# Sche.net
KiCad netlist of a schematic drawn in Altium Designer
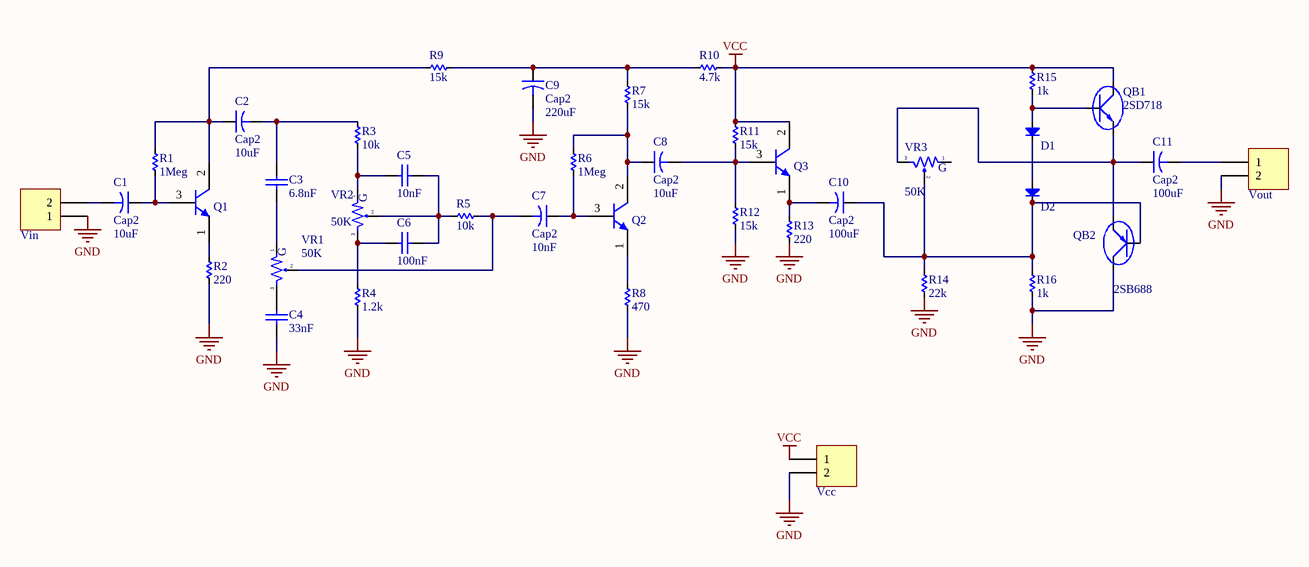
[diagram p0: Sche.SchDoc]

(export (version "E")
  (design (tool "Eeschema 10.0.6"))
  (components
    (comp (ref "C1")
      (value "Cap2")
      (footprint "CAPR5-4X5")
      (description "Capacitor")
      (fields (field (name "ALTIUM_VALUE") "10uF") (field (name "PUBLISHER") "Altium Limited"))
      (libsource (lib "Miscellaneous Devices") (part "Cap2"))
    )
    (comp (ref "C2")
      (value "Cap2")
      (footprint "CAPR5-4X5")
      (description "Capacitor")
      (fields (field (name "ALTIUM_VALUE") "10uF") (field (name "PUBLISHER") "Altium Limited"))
      (libsource (lib "Miscellaneous Devices") (part "Cap2"))
    )
    (comp (ref "C3")
      (value "6.8nF")
      (footprint "CN1.5")
      (description "Capacitor")
      (fields (field (name "Comment") "Cap Non-Pol"))
      (libsource (lib "PIF_Library") (part "Cap Non-Pol"))
    )
    (comp (ref "C4")
      (value "33nF")
      (footprint "CN1.5")
      (description "Capacitor")
      (fields (field (name "Comment") "Cap Non-Pol"))
      (libsource (lib "PIF_Library") (part "Cap Non-Pol"))
    )
    (comp (ref "C5")
      (value "10nF")
      (footprint "CN1.5")
      (description "Capacitor")
      (fields (field (name "Comment") "Cap Non-Pol"))
      (libsource (lib "PIF_Library") (part "Cap Non-Pol"))
    )
    (comp (ref "C6")
      (value "100nF")
      (footprint "CN1.5")
      (description "Capacitor")
      (fields (field (name "Comment") "Cap Non-Pol"))
      (libsource (lib "PIF_Library") (part "Cap Non-Pol"))
    )
    (comp (ref "C7")
      (value "Cap2")
      (footprint "CAPR5-4X5")
      (description "Capacitor")
      (fields (field (name "ALTIUM_VALUE") "10nF") (field (name "PUBLISHER") "Altium Limited"))
      (libsource (lib "Miscellaneous Devices") (part "Cap2"))
    )
    (comp (ref "C8")
      (value "Cap2")
      (footprint "CAPR5-4X5")
      (description "Capacitor")
      (fields (field (name "ALTIUM_VALUE") "10uF") (field (name "PUBLISHER") "Altium Limited"))
      (libsource (lib "Miscellaneous Devices") (part "Cap2"))
    )
    (comp (ref "C9")
      (value "Cap2")
      (footprint "CAPR5-4X5")
      (description "Capacitor")
      (fields (field (name "ALTIUM_VALUE") "220uF") (field (name "PUBLISHER") "Altium Limited"))
      (libsource (lib "Miscellaneous Devices") (part "Cap2"))
    )
    (comp (ref "C10")
      (value "Cap2")
      (footprint "CAPR5-4X5")
      (description "Capacitor")
      (fields (field (name "ALTIUM_VALUE") "100uF") (field (name "PUBLISHER") "Altium Limited"))
      (libsource (lib "Miscellaneous Devices") (part "Cap2"))
    )
    (comp (ref "C11")
      (value "Cap2")
      (footprint "CAPR5-4X5")
      (description "Capacitor")
      (fields (field (name "ALTIUM_VALUE") "100uF") (field (name "PUBLISHER") "Altium Limited"))
      (libsource (lib "Miscellaneous Devices") (part "Cap2"))
    )
    (comp (ref "D1")
      (value "Diode")
      (footprint "DIO-1A")
      (description "Default Diode")
      (fields (field (name "PUBLISHER") "Altium Limited"))
      (libsource (lib "LIBRARY") (part "Diode"))
    )
    (comp (ref "D2")
      (value "Diode")
      (footprint "DIO-1A")
      (description "Default Diode")
      (fields (field (name "PUBLISHER") "Altium Limited"))
      (libsource (lib "LIBRARY") (part "Diode"))
    )
    (comp (ref "Q1")
      (value "C1815")
      (footprint "QTO-92")
      (description "NPN Bipolar Transistor")
      (libsource (lib "PIF_Library") (part "C1815"))
    )
    (comp (ref "Q2")
      (value "C1815")
      (footprint "QTO-92")
      (description "NPN Bipolar Transistor")
      (libsource (lib "PIF_Library") (part "C1815"))
    )
    (comp (ref "Q3")
      (value "C1815")
      (footprint "QTO-92")
      (description "NPN Bipolar Transistor")
      (libsource (lib "PIF_Library") (part "C1815"))
    )
    (comp (ref "QB1")
      (value "2SD718")
      (footprint "TO247h")
      (description "Transistor Power Supply")
      (libsource (lib "LIBRARY") (part "2SC5200"))
    )
    (comp (ref "QB2")
      (value "2SB688")
      (footprint "TO247h")
      (description "Transistor Power Supply")
      (libsource (lib "LIBRARY") (part "2SB688"))
    )
    (comp (ref "R1")
      (value "1Meg")
      (footprint "RES-SMD-0805")
      (description "Resistor")
      (fields
        (field (name "MANUFACTURER") "Generic Components")
        (field (name "PUBLISHER") "Altium Hobart Technology Centre")
      )
      (libsource (lib "LIBRARY") (part "Res-SMD"))
    )
    (comp (ref "R2")
      (value "220")
      (footprint "RES-SMD-0805")
      (description "Resistor")
      (fields
        (field (name "MANUFACTURER") "Generic Components")
        (field (name "PUBLISHER") "Altium Hobart Technology Centre")
      )
      (libsource (lib "LIBRARY") (part "Res-SMD"))
    )
    (comp (ref "R3")
      (value "10k")
      (footprint "RES-SMD-0805")
      (description "Resistor")
      (fields
        (field (name "MANUFACTURER") "Generic Components")
        (field (name "PUBLISHER") "Altium Hobart Technology Centre")
      )
      (libsource (lib "LIBRARY") (part "Res-SMD"))
    )
    (comp (ref "R4")
      (value "1.2k")
      (footprint "RES-SMD-0805")
      (description "Resistor")
      (fields
        (field (name "MANUFACTURER") "Generic Components")
        (field (name "PUBLISHER") "Altium Hobart Technology Centre")
      )
      (libsource (lib "LIBRARY") (part "Res-SMD"))
    )
    (comp (ref "R5")
      (value "10k")
      (footprint "RES-SMD-0805")
      (description "Resistor")
      (fields
        (field (name "MANUFACTURER") "Generic Components")
        (field (name "PUBLISHER") "Altium Hobart Technology Centre")
      )
      (libsource (lib "LIBRARY") (part "Res-SMD"))
    )
    (comp (ref "R6")
      (value "1Meg")
      (footprint "RES-SMD-0805")
      (description "Resistor")
      (fields
        (field (name "MANUFACTURER") "Generic Components")
        (field (name "PUBLISHER") "Altium Hobart Technology Centre")
      )
      (libsource (lib "LIBRARY") (part "Res-SMD"))
    )
    (comp (ref "R7")
      (value "15k")
      (footprint "RES-SMD-0805")
      (description "Resistor")
      (fields
        (field (name "MANUFACTURER") "Generic Components")
        (field (name "PUBLISHER") "Altium Hobart Technology Centre")
      )
      (libsource (lib "LIBRARY") (part "Res-SMD"))
    )
    (comp (ref "R8")
      (value "470")
      (footprint "RES-SMD-0805")
      (description "Resistor")
      (fields
        (field (name "MANUFACTURER") "Generic Components")
        (field (name "PUBLISHER") "Altium Hobart Technology Centre")
      )
      (libsource (lib "LIBRARY") (part "Res-SMD"))
    )
    (comp (ref "R9")
      (value "15k")
      (footprint "RES-SMD-0805")
      (description "Resistor")
      (fields
        (field (name "MANUFACTURER") "Generic Components")
        (field (name "PUBLISHER") "Altium Hobart Technology Centre")
      )
      (libsource (lib "LIBRARY") (part "Res-SMD"))
    )
    (comp (ref "R10")
      (value "4.7k")
      (footprint "RES-SMD-0805")
      (description "Resistor")
      (fields
        (field (name "MANUFACTURER") "Generic Components")
        (field (name "PUBLISHER") "Altium Hobart Technology Centre")
      )
      (libsource (lib "LIBRARY") (part "Res-SMD"))
    )
    (comp (ref "R11")
      (value "15k")
      (footprint "RES-SMD-0805")
      (description "Resistor")
      (fields
        (field (name "MANUFACTURER") "Generic Components")
        (field (name "PUBLISHER") "Altium Hobart Technology Centre")
      )
      (libsource (lib "LIBRARY") (part "Res-SMD"))
    )
    (comp (ref "R12")
      (value "15k")
      (footprint "RES-SMD-0805")
      (description "Resistor")
      (fields
        (field (name "MANUFACTURER") "Generic Components")
        (field (name "PUBLISHER") "Altium Hobart Technology Centre")
      )
      (libsource (lib "LIBRARY") (part "Res-SMD"))
    )
    (comp (ref "R13")
      (value "220")
      (footprint "RES-SMD-0805")
      (description "Resistor")
      (fields
        (field (name "MANUFACTURER") "Generic Components")
        (field (name "PUBLISHER") "Altium Hobart Technology Centre")
      )
      (libsource (lib "LIBRARY") (part "Res-SMD"))
    )
    (comp (ref "R14")
      (value "22k")
      (footprint "RES-SMD-0805")
      (description "Resistor")
      (fields
        (field (name "MANUFACTURER") "Generic Components")
        (field (name "PUBLISHER") "Altium Hobart Technology Centre")
      )
      (libsource (lib "LIBRARY") (part "Res-SMD"))
    )
    (comp (ref "R15")
      (value "1k")
      (footprint "RES-SMD-0805")
      (description "Resistor")
      (fields
        (field (name "MANUFACTURER") "Generic Components")
        (field (name "PUBLISHER") "Altium Hobart Technology Centre")
      )
      (libsource (lib "LIBRARY") (part "Res-SMD"))
    )
    (comp (ref "R16")
      (value "1k")
      (footprint "RES-SMD-0805")
      (description "Resistor")
      (fields
        (field (name "MANUFACTURER") "Generic Components")
        (field (name "PUBLISHER") "Altium Hobart Technology Centre")
      )
      (libsource (lib "LIBRARY") (part "Res-SMD"))
    )
    (comp (ref "Vcc")
      (value "Domino 2")
      (footprint "DOMINO 2- 5mm")
      (description "Domino, 2-Pin")
      (fields (field (name "PUBLISHER") "Altium Limited"))
      (libsource (lib "PIF_Library") (part "Domino 2"))
    )
    (comp (ref "Vin")
      (value "Domino 2")
      (footprint "DOMINO 2- 5mm")
      (description "Domino, 2-Pin")
      (fields (field (name "PUBLISHER") "Altium Limited"))
      (libsource (lib "") (part "Domino 2_1"))
    )
    (comp (ref "Vout")
      (value "Domino 2")
      (footprint "DOMINO 2- 5mm")
      (description "Domino, 2-Pin")
      (fields (field (name "PUBLISHER") "Altium Limited"))
      (libsource (lib "PIF_Library") (part "Domino 2"))
    )
    (comp (ref "VR1")
      (value "50K")
      (footprint "VR-S1")
      (description "Var Resistor")
      (libsource (lib "LIBRARY") (part "VR-S"))
    )
    (comp (ref "VR2")
      (value "50K")
      (footprint "VR-S1")
      (description "Var Resistor")
      (libsource (lib "LIBRARY") (part "VR-S"))
    )
    (comp (ref "VR3")
      (value "50K")
      (footprint "VR-S1")
      (description "Var Resistor")
      (libsource (lib "LIBRARY") (part "VR-S"))
    )
  )
  (nets
    (net (code "1") (name "GND") (class "Default")
      (node (ref "C4") (pin "1") (pinfunction "1_1") (pintype "passive"))
      (node (ref "C9") (pin "2") (pinfunction "2_2") (pintype "passive"))
      (node (ref "QB2") (pin "2") (pinfunction "C_2") (pintype "passive"))
      (node (ref "R12") (pin "2") (pinfunction "2_2") (pintype "passive"))
      (node (ref "R13") (pin "2") (pinfunction "2_2") (pintype "passive"))
      (node (ref "R14") (pin "2") (pinfunction "2_2") (pintype "passive"))
      (node (ref "R16") (pin "2") (pinfunction "2_2") (pintype "passive"))
      (node (ref "R2") (pin "2") (pinfunction "2_2") (pintype "passive"))
      (node (ref "R4") (pin "2") (pinfunction "2_2") (pintype "passive"))
      (node (ref "R8") (pin "2") (pinfunction "2_2") (pintype "passive"))
      (node (ref "Vcc") (pin "2") (pinfunction "2_2") (pintype "passive"))
      (node (ref "Vin") (pin "1") (pinfunction "1_1") (pintype "passive"))
      (node (ref "Vout") (pin "2") (pinfunction "2_2") (pintype "passive"))
    )
    (net (code "2") (name "Net-(C1-Pad2)") (class "Default")
      (node (ref "C1") (pin "2") (pinfunction "2_2") (pintype "passive"))
      (node (ref "Vin") (pin "2") (pinfunction "2_2") (pintype "passive"))
    )
    (net (code "3") (name "Net-(C2-Pad2)") (class "Default")
      (node (ref "C2") (pin "2") (pinfunction "2_2") (pintype "passive"))
      (node (ref "C3") (pin "2") (pinfunction "2_2") (pintype "passive"))
      (node (ref "R3") (pin "1") (pinfunction "1_1") (pintype "passive"))
    )
    (net (code "4") (name "Net-(C3-Pad1)") (class "Default")
      (node (ref "C3") (pin "1") (pinfunction "1_1") (pintype "passive"))
      (node (ref "VR1") (pin "1") (pinfunction "1_1") (pintype "passive"))
    )
    (net (code "5") (name "Net-(C4-Pad2)") (class "Default")
      (node (ref "C4") (pin "2") (pinfunction "2_2") (pintype "passive"))
      (node (ref "VR1") (pin "3") (pinfunction "3_3") (pintype "passive"))
    )
    (net (code "6") (name "Net-(C5-Pad1)") (class "Default")
      (node (ref "C5") (pin "1") (pinfunction "1_1") (pintype "passive"))
      (node (ref "R3") (pin "2") (pinfunction "2_2") (pintype "passive"))
      (node (ref "VR2") (pin "1") (pinfunction "1_1") (pintype "passive"))
    )
    (net (code "7") (name "Net-(C5-Pad2)") (class "Default")
      (node (ref "C5") (pin "2") (pinfunction "2_2") (pintype "passive"))
      (node (ref "C6") (pin "2") (pinfunction "2_2") (pintype "passive"))
      (node (ref "R5") (pin "2") (pinfunction "2_2") (pintype "passive"))
      (node (ref "VR2") (pin "2") (pinfunction "2_2") (pintype "passive"))
    )
    (net (code "8") (name "Net-(C6-Pad1)") (class "Default")
      (node (ref "C6") (pin "1") (pinfunction "1_1") (pintype "passive"))
      (node (ref "R4") (pin "1") (pinfunction "1_1") (pintype "passive"))
      (node (ref "VR2") (pin "3") (pinfunction "3_3") (pintype "passive"))
    )
    (net (code "9") (name "Net-(C7-Pad2)") (class "Default")
      (node (ref "C7") (pin "2") (pinfunction "2_2") (pintype "passive"))
      (node (ref "R5") (pin "1") (pinfunction "1_1") (pintype "passive"))
      (node (ref "VR1") (pin "2") (pinfunction "2_2") (pintype "passive"))
    )
    (net (code "10") (name "Net-(C9-Pad1)") (class "Default")
      (node (ref "C9") (pin "1") (pinfunction "1_1") (pintype "passive"))
      (node (ref "R10") (pin "2") (pinfunction "2_2") (pintype "passive"))
      (node (ref "R7") (pin "1") (pinfunction "1_1") (pintype "passive"))
      (node (ref "R9") (pin "1") (pinfunction "1_1") (pintype "passive"))
    )
    (net (code "11") (name "Net-(C11-Pad2)") (class "Default")
      (node (ref "C11") (pin "2") (pinfunction "2_2") (pintype "passive"))
      (node (ref "Vout") (pin "1") (pinfunction "1_1") (pintype "passive"))
    )
    (net (code "12") (name "Net-(D1-A)") (class "Default")
      (node (ref "D1") (pin "1") (pinfunction "A_1") (pintype "passive"))
      (node (ref "QB1") (pin "1") (pinfunction "B_1") (pintype "passive"))
      (node (ref "R15") (pin "2") (pinfunction "2_2") (pintype "passive"))
    )
    (net (code "13") (name "Net-(D1-K)") (class "Default")
      (node (ref "D1") (pin "2") (pinfunction "K_2") (pintype "passive"))
      (node (ref "D2") (pin "1") (pinfunction "A_1") (pintype "passive"))
    )
    (net (code "14") (name "Net-(D2-K)") (class "Default")
      (node (ref "C10") (pin "1") (pinfunction "1_1") (pintype "passive"))
      (node (ref "D2") (pin "2") (pinfunction "K_2") (pintype "passive"))
      (node (ref "QB2") (pin "1") (pinfunction "B_1") (pintype "passive"))
      (node (ref "R14") (pin "1") (pinfunction "1_1") (pintype "passive"))
      (node (ref "R16") (pin "1") (pinfunction "1_1") (pintype "passive"))
      (node (ref "VR3") (pin "2") (pinfunction "2_2") (pintype "passive"))
    )
    (net (code "15") (name "Net-(Q1-B)") (class "Default")
      (node (ref "C1") (pin "1") (pinfunction "1_1") (pintype "passive"))
      (node (ref "Q1") (pin "3") (pinfunction "B_3") (pintype "passive"))
      (node (ref "R1") (pin "2") (pinfunction "2_2") (pintype "passive"))
    )
    (net (code "16") (name "Net-(Q1-C)") (class "Default")
      (node (ref "C2") (pin "1") (pinfunction "1_1") (pintype "passive"))
      (node (ref "Q1") (pin "2") (pinfunction "C_2") (pintype "passive"))
      (node (ref "R1") (pin "1") (pinfunction "1_1") (pintype "passive"))
      (node (ref "R9") (pin "2") (pinfunction "2_2") (pintype "passive"))
    )
    (net (code "17") (name "Net-(Q1-E)") (class "Default")
      (node (ref "Q1") (pin "1") (pinfunction "E_1") (pintype "passive"))
      (node (ref "R2") (pin "1") (pinfunction "1_1") (pintype "passive"))
    )
    (net (code "18") (name "Net-(Q2-B)") (class "Default")
      (node (ref "C7") (pin "1") (pinfunction "1_1") (pintype "passive"))
      (node (ref "Q2") (pin "3") (pinfunction "B_3") (pintype "passive"))
      (node (ref "R6") (pin "2") (pinfunction "2_2") (pintype "passive"))
    )
    (net (code "19") (name "Net-(Q2-C)") (class "Default")
      (node (ref "C8") (pin "1") (pinfunction "1_1") (pintype "passive"))
      (node (ref "Q2") (pin "2") (pinfunction "C_2") (pintype "passive"))
      (node (ref "R6") (pin "1") (pinfunction "1_1") (pintype "passive"))
      (node (ref "R7") (pin "2") (pinfunction "2_2") (pintype "passive"))
    )
    (net (code "20") (name "Net-(Q2-E)") (class "Default")
      (node (ref "Q2") (pin "1") (pinfunction "E_1") (pintype "passive"))
      (node (ref "R8") (pin "1") (pinfunction "1_1") (pintype "passive"))
    )
    (net (code "21") (name "Net-(Q3-B)") (class "Default")
      (node (ref "C8") (pin "2") (pinfunction "2_2") (pintype "passive"))
      (node (ref "Q3") (pin "3") (pinfunction "B_3") (pintype "passive"))
      (node (ref "R11") (pin "2") (pinfunction "2_2") (pintype "passive"))
      (node (ref "R12") (pin "1") (pinfunction "1_1") (pintype "passive"))
    )
    (net (code "22") (name "Net-(Q3-E)") (class "Default")
      (node (ref "C10") (pin "2") (pinfunction "2_2") (pintype "passive"))
      (node (ref "Q3") (pin "1") (pinfunction "E_1") (pintype "passive"))
      (node (ref "R13") (pin "1") (pinfunction "1_1") (pintype "passive"))
    )
    (net (code "23") (name "Net-(QB1-E)") (class "Default")
      (node (ref "C11") (pin "1") (pinfunction "1_1") (pintype "passive"))
      (node (ref "QB1") (pin "3") (pinfunction "E_3") (pintype "passive"))
      (node (ref "QB2") (pin "3") (pinfunction "E_3") (pintype "passive"))
      (node (ref "VR3") (pin "3") (pinfunction "3_3") (pintype "passive"))
    )
    (net (code "24") (name "VCC") (class "Default")
      (node (ref "Q3") (pin "2") (pinfunction "C_2") (pintype "passive"))
      (node (ref "QB1") (pin "2") (pinfunction "C_2") (pintype "passive"))
      (node (ref "R10") (pin "1") (pinfunction "1_1") (pintype "passive"))
      (node (ref "R11") (pin "1") (pinfunction "1_1") (pintype "passive"))
      (node (ref "R15") (pin "1") (pinfunction "1_1") (pintype "passive"))
      (node (ref "Vcc") (pin "1") (pinfunction "1_1") (pintype "passive"))
    )
    (net (code "25") (name "unconnected-(VR3-Pad1)") (class "Default")
      (node (ref "VR3") (pin "1") (pinfunction "1_1") (pintype "passive"))
    )
  )
)
